# ts-50s-digi-interface.net
KiCad netlist of a schematic drawn in Altium Designer
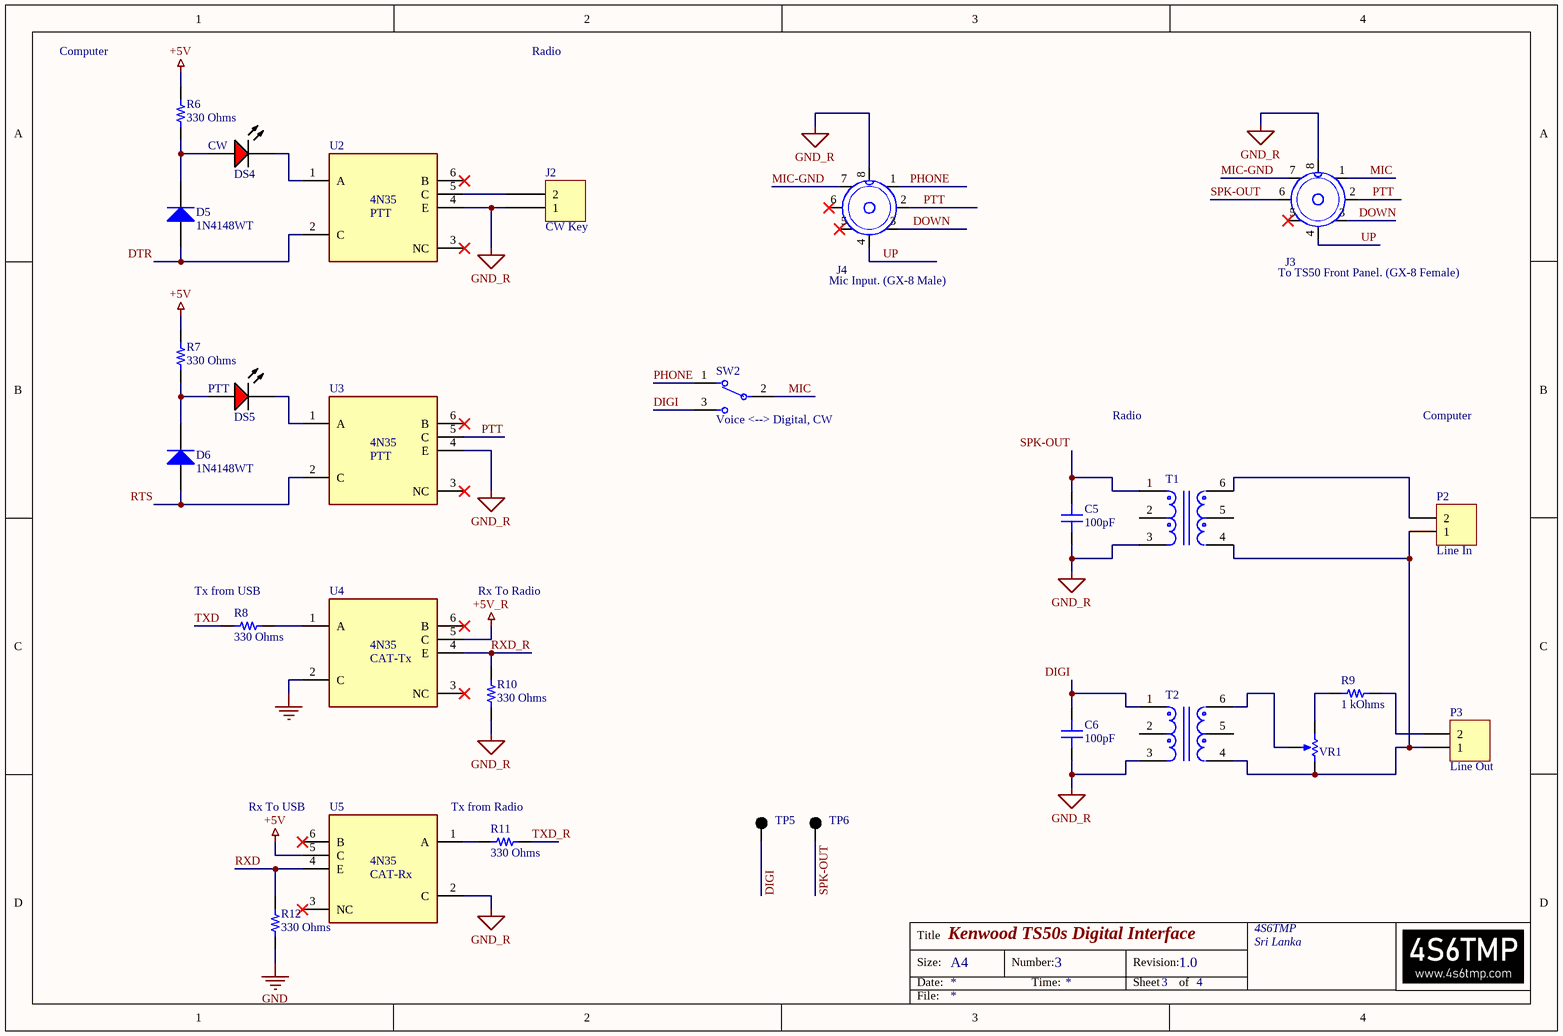
[diagram p0: ts-50s-digi-interface.SchDoc]

(export (version "E")
  (design (tool "Eeschema 10.0.6"))
  (components
    (comp (ref "C5")
      (value "100pF")
      (footprint "CAP 0603_1608")
      (description "CAP CER 100PF 50V C0G/NP0 0603")
      (fields
        (field (name "PART NUMBER") "500R14N101JV4T")
        (field (name "MANUFACTURER") "Johanson Dielectrics Inc.")
      )
      (libsource (lib "Celestial Altium Library - altium_library") (part "Capacitor"))
    )
    (comp (ref "C6")
      (value "100pF")
      (footprint "CAP 0603_1608")
      (description "CAP CER 100PF 50V C0G/NP0 0603")
      (fields
        (field (name "PART NUMBER") "500R14N101JV4T")
        (field (name "MANUFACTURER") "Johanson Dielectrics Inc.")
      )
      (libsource (lib "Celestial Altium Library - altium_library") (part "Capacitor"))
    )
    (comp (ref "D5")
      (value "1N4148WT")
      (footprint "FAIR-SOD-523F-2_V")
      (description "High Conductance Fast Switching Diode, 75 V, -55 to 150 degC, 2-Pin SOD523F, RoHS")
      (fields (field (name "MANUFACTURER") "Fairchild Semiconductor"))
      (libsource (lib "Altium Content Vault") (part "FAIR-D_K1A2-2"))
    )
    (comp (ref "D6")
      (value "1N4148WT")
      (footprint "FAIR-SOD-523F-2_V")
      (description "High Conductance Fast Switching Diode, 75 V, -55 to 150 degC, 2-Pin SOD523F, RoHS")
      (fields (field (name "MANUFACTURER") "Fairchild Semiconductor"))
      (libsource (lib "Altium Content Vault") (part "FAIR-D_K1A2-2"))
    )
    (comp (ref "DS4")
      (value "CW")
      (footprint "AVAG-HLMP-3301-2")
      (description "T-1 3/4 (5 mm) Diffused LED Lamp, 1.9 V, -40 to 100 degC, 2-Pin THD, RoHS, Bulk")
      (fields (field (name "MANUFACTURER") "Avago"))
      (libsource (lib "Altium Content Vault") (part "LED-RED-K1A2-2"))
    )
    (comp (ref "DS5")
      (value "PTT")
      (footprint "AVAG-HLMP-3301-2")
      (description "T-1 3/4 (5 mm) Diffused LED Lamp, 1.9 V, -40 to 100 degC, 2-Pin THD, RoHS, Bulk")
      (fields (field (name "MANUFACTURER") "Avago"))
      (libsource (lib "Altium Content Vault") (part "LED-RED-K1A2-2"))
    )
    (comp (ref "J2")
      (value "CW Key")
      (footprint "MOLEX KK 0022272021")
      (description "CONN HEADER VERT 2POS 2.54MM")
      (fields (field (name "PART NUMBER") "0022272021") (field (name "MANUFACTURER") "Molex"))
      (libsource (lib "Celestial Altium Library - altium_library") (part "2 Pin"))
    )
    (comp (ref "J3")
      (value "To TS50 Front Panel. (GX-8 Female)")
      (footprint "GX-8")
      (description "8 Position Circular Connector Receptacle, Male Pins Solder")
      (fields (field (name "MANUFACTURER") "Amphenol Tuchel Industrial"))
      (libsource (lib "GX-8") (part "GX-8"))
    )
    (comp (ref "J4")
      (value "Mic Input. (GX-8 Male)")
      (footprint "GX-8")
      (description "8 Position Circular Connector Receptacle, Male Pins Solder")
      (fields (field (name "MANUFACTURER") "Amphenol Tuchel Industrial"))
      (libsource (lib "GX-8") (part "GX-8"))
    )
    (comp (ref "P2")
      (value "Line In")
      (footprint "HDR1X2")
      (description "3.5mm Mono")
      (fields (field (name "PUBLISHER") "Altium Limited"))
      (libsource (lib "Miscellaneous Connectors") (part "Header 2"))
    )
    (comp (ref "P3")
      (value "Line Out")
      (footprint "HDR1X2")
      (description "3.5mm Mono")
      (fields (field (name "PUBLISHER") "Altium Limited"))
      (libsource (lib "Miscellaneous Connectors") (part "Header 2"))
    )
    (comp (ref "R6")
      (value "330 Ohms")
      (footprint "RES 0603_1608")
      (description "RES SMD 330 OHM 1% 1/10W 0603")
      (fields (field (name "PART NUMBER") "AC0603FR-07330RL") (field (name "MANUFACTURER") "Yageo"))
      (libsource (lib "Celestial Altium Library - altium_library") (part "Resistor"))
    )
    (comp (ref "R7")
      (value "330 Ohms")
      (footprint "RES 0603_1608")
      (description "RES SMD 330 OHM 1% 1/10W 0603")
      (fields (field (name "PART NUMBER") "AC0603FR-07330RL") (field (name "MANUFACTURER") "Yageo"))
      (libsource (lib "Celestial Altium Library - altium_library") (part "Resistor"))
    )
    (comp (ref "R8")
      (value "330 Ohms")
      (footprint "RES 0603_1608")
      (description "RES SMD 330 OHM 1% 1/10W 0603")
      (fields (field (name "PART NUMBER") "AC0603FR-07330RL") (field (name "MANUFACTURER") "Yageo"))
      (libsource (lib "Celestial Altium Library - altium_library") (part "Resistor"))
    )
    (comp (ref "R9")
      (value "1 kOhms")
      (footprint "RES 0603_1608")
      (description "RES SMD 1K OHM 1% 1/10W 0603")
      (fields (field (name "PART NUMBER") "AT0603FRE071KL") (field (name "MANUFACTURER") "Yageo"))
      (libsource (lib "Celestial Altium Library - altium_library") (part "Resistor"))
    )
    (comp (ref "R10")
      (value "330 Ohms")
      (footprint "RES 0603_1608")
      (description "RES SMD 330 OHM 1% 1/10W 0603")
      (fields (field (name "PART NUMBER") "AC0603FR-07330RL") (field (name "MANUFACTURER") "Yageo"))
      (libsource (lib "Celestial Altium Library - altium_library") (part "Resistor"))
    )
    (comp (ref "R11")
      (value "330 Ohms")
      (footprint "RES 0603_1608")
      (description "RES SMD 330 OHM 1% 1/10W 0603")
      (fields (field (name "PART NUMBER") "AC0603FR-07330RL") (field (name "MANUFACTURER") "Yageo"))
      (libsource (lib "Celestial Altium Library - altium_library") (part "Resistor"))
    )
    (comp (ref "R12")
      (value "330 Ohms")
      (footprint "RES 0603_1608")
      (description "RES SMD 330 OHM 1% 1/10W 0603")
      (fields (field (name "PART NUMBER") "AC0603FR-07330RL") (field (name "MANUFACTURER") "Yageo"))
      (libsource (lib "Celestial Altium Library - altium_library") (part "Resistor"))
    )
    (comp (ref "SW2")
      (value "Voice <--> Digital, CW")
      (footprint "FP-A101SDCQ04-MFG")
      (description "SWITCH TOGGLE SPDT 5A 120V")
      (libsource (lib "Altium Content Vault") (part "52c419afdc2a387c7d548259a9aeefb"))
    )
    (comp (ref "T1")
      (value "SM-LP-5001")
      (footprint "SM-LP-5001")
      (description "TRANSFORMER LINE MATCHING SMD")
      (libsource (lib "SM-LP-5001") (part "CMP-07264-000002-1"))
    )
    (comp (ref "T2")
      (value "SM-LP-5001")
      (footprint "SM-LP-5001")
      (description "TRANSFORMER LINE MATCHING SMD")
      (libsource (lib "SM-LP-5001") (part "CMP-07264-000002-1"))
    )
    (comp (ref "TP5")
      (value "DIGI")
      (footprint "KSTN-5001")
      (description "Test Point, Black, 1-Pin THD, RoHS, Bulk")
      (fields (field (name "MANUFACTURER") "Keystone"))
      (libsource (lib "Altium Content Vault") (part "KSTN-TP-5001"))
    )
    (comp (ref "TP6")
      (value "SPK OUT")
      (footprint "KSTN-5001")
      (description "Test Point, Black, 1-Pin THD, RoHS, Bulk")
      (fields (field (name "MANUFACTURER") "Keystone"))
      (libsource (lib "Altium Content Vault") (part "KSTN-TP-5001"))
    )
    (comp (ref "U2")
      (value "PTT")
      (footprint "Vishay_4N35_0")
      (description "IC OPTOISO 5KV TRANS W/BASE 6DIP")
      (fields
        (field (name "MANUFACTURER") "Vishay")
        (field (name "MOUSER PART NUMBER") "78-4N35")
        (field (name "PART NUMBER") "4N35")
      )
      (libsource (lib "") (part "IC_Vishay_4N35_eec_1"))
    )
    (comp (ref "U3")
      (value "PTT")
      (footprint "Vishay_4N35_0")
      (description "IC OPTOISO 5KV TRANS W/BASE 6DIP")
      (fields
        (field (name "MANUFACTURER") "Vishay")
        (field (name "MOUSER PART NUMBER") "78-4N35")
        (field (name "PART NUMBER") "4N35")
      )
      (libsource (lib "") (part "IC_Vishay_4N35_eec_1"))
    )
    (comp (ref "U4")
      (value "CAT-Tx")
      (footprint "Vishay_4N35_0")
      (description "IC OPTOISO 5KV TRANS W/BASE 6DIP")
      (fields
        (field (name "MANUFACTURER") "Vishay")
        (field (name "MOUSER PART NUMBER") "78-4N35")
        (field (name "PART NUMBER") "4N35")
      )
      (libsource (lib "") (part "IC_Vishay_4N35_eec_1"))
    )
    (comp (ref "U5")
      (value "CAT-Rx")
      (footprint "Vishay_4N35_0")
      (description "IC OPTOISO 5KV TRANS W/BASE 6DIP")
      (fields
        (field (name "MANUFACTURER") "Vishay")
        (field (name "MOUSER PART NUMBER") "78-4N35")
        (field (name "PART NUMBER") "4N35")
      )
      (libsource (lib "Optocouplers") (part "IC_Vishay_4N35_eec"))
    )
    (comp (ref "VR1")
      (value "3852A-282-103AL")
      (footprint "BOUR-3852A-282-103AL-3_V")
      (description "Diameter Panel Control, 100 KOhm, +/- 10%, 2 W, -1 to 125 degC, 3-Pin THD, RoHS, Bulk")
      (fields (field (name "TOLERANCE") "±10%") (field (name "MANUFACTURER") "Bourns"))
      (libsource (lib "Altium Content Vault") (part "RES-POT-3"))
    )
  )
  (nets
    (net (code "1") (name "+5V") (class "Default")
      (node (ref "R6") (pin "2") (pinfunction "2_2") (pintype "passive"))
      (node (ref "R7") (pin "2") (pinfunction "2_2") (pintype "passive"))
      (node (ref "U5") (pin "5") (pinfunction "C_5") (pintype "passive"))
    )
    (net (code "2") (name "+5V_R") (class "Default")
      (node (ref "U4") (pin "5") (pinfunction "C_5") (pintype "passive"))
    )
    (net (code "3") (name "/DIGI") (class "Default")
      (node (ref "C6") (pin "2") (pinfunction "2_2") (pintype "passive"))
      (node (ref "SW2") (pin "3") (pinfunction "3_3") (pintype "passive"))
      (node (ref "T2") (pin "1") (pinfunction "1_1") (pintype "passive"))
      (node (ref "TP5") (pin "1") (pintype "passive"))
    )
    (net (code "4") (name "/DOWN") (class "Default")
      (node (ref "J3") (pin "3") (pinfunction "3_3") (pintype "passive"))
      (node (ref "J4") (pin "3") (pinfunction "3_3") (pintype "passive"))
    )
    (net (code "5") (name "/DTR") (class "Default")
      (node (ref "D5") (pin "2") (pinfunction "A_2") (pintype "passive"))
      (node (ref "U2") (pin "2") (pinfunction "C_2") (pintype "passive"))
    )
    (net (code "6") (name "/MIC") (class "Default")
      (node (ref "J3") (pin "1") (pinfunction "1_1") (pintype "passive"))
      (node (ref "SW2") (pin "2") (pinfunction "2_2") (pintype "passive"))
    )
    (net (code "7") (name "/MIC-GND") (class "Default")
      (node (ref "J3") (pin "7") (pinfunction "7_7") (pintype "passive"))
      (node (ref "J4") (pin "7") (pinfunction "7_7") (pintype "passive"))
    )
    (net (code "8") (name "/PHONE") (class "Default")
      (node (ref "J4") (pin "1") (pinfunction "1_1") (pintype "passive"))
      (node (ref "SW2") (pin "1") (pinfunction "1_1") (pintype "passive"))
    )
    (net (code "9") (name "/PTT") (class "Default")
      (node (ref "J3") (pin "2") (pinfunction "2_2") (pintype "passive"))
      (node (ref "J4") (pin "2") (pinfunction "2_2") (pintype "passive"))
      (node (ref "U3") (pin "5") (pinfunction "C_5") (pintype "passive"))
    )
    (net (code "10") (name "/RTS") (class "Default")
      (node (ref "D6") (pin "2") (pinfunction "A_2") (pintype "passive"))
      (node (ref "U3") (pin "2") (pinfunction "C_2") (pintype "passive"))
    )
    (net (code "11") (name "/RXD") (class "Default")
      (node (ref "R12") (pin "1") (pinfunction "1_1") (pintype "passive"))
      (node (ref "U5") (pin "4") (pinfunction "E_4") (pintype "passive"))
    )
    (net (code "12") (name "/RXD_R") (class "Default")
      (node (ref "R10") (pin "1") (pinfunction "1_1") (pintype "passive"))
      (node (ref "U4") (pin "4") (pinfunction "E_4") (pintype "passive"))
    )
    (net (code "13") (name "/SPK-OUT") (class "Default")
      (node (ref "C5") (pin "2") (pinfunction "2_2") (pintype "passive"))
      (node (ref "J3") (pin "6") (pinfunction "6_6") (pintype "passive"))
      (node (ref "T1") (pin "1") (pinfunction "1_1") (pintype "passive"))
      (node (ref "TP6") (pin "1") (pintype "passive"))
    )
    (net (code "14") (name "/TXD") (class "Default")
      (node (ref "R8") (pin "2") (pinfunction "2_2") (pintype "passive"))
    )
    (net (code "15") (name "/TXD_R") (class "Default")
      (node (ref "R11") (pin "1") (pinfunction "1_1") (pintype "passive"))
    )
    (net (code "16") (name "/UP") (class "Default")
      (node (ref "J3") (pin "4") (pinfunction "4_4") (pintype "passive"))
      (node (ref "J4") (pin "4") (pinfunction "4_4") (pintype "passive"))
    )
    (net (code "17") (name "GND") (class "Default")
      (node (ref "R12") (pin "2") (pinfunction "2_2") (pintype "passive"))
      (node (ref "U4") (pin "2") (pinfunction "C_2") (pintype "passive"))
    )
    (net (code "18") (name "GND_R") (class "Default")
      (node (ref "C5") (pin "1") (pinfunction "1_1") (pintype "passive"))
      (node (ref "C6") (pin "1") (pinfunction "1_1") (pintype "passive"))
      (node (ref "J2") (pin "1") (pinfunction "1_1") (pintype "passive"))
      (node (ref "J3") (pin "8") (pinfunction "8_8") (pintype "passive"))
      (node (ref "J4") (pin "8") (pinfunction "8_8") (pintype "passive"))
      (node (ref "R10") (pin "2") (pinfunction "2_2") (pintype "passive"))
      (node (ref "T1") (pin "3") (pinfunction "3_3") (pintype "passive"))
      (node (ref "T2") (pin "3") (pinfunction "3_3") (pintype "passive"))
      (node (ref "U2") (pin "4") (pinfunction "E_4") (pintype "passive"))
      (node (ref "U3") (pin "4") (pinfunction "E_4") (pintype "passive"))
      (node (ref "U5") (pin "2") (pinfunction "C_2") (pintype "passive"))
    )
    (net (code "19") (name "Net-(D5-K)") (class "Default")
      (node (ref "D5") (pin "1") (pinfunction "K_1") (pintype "passive"))
      (node (ref "DS4") (pin "2") (pinfunction "A_2") (pintype "passive"))
      (node (ref "R6") (pin "1") (pinfunction "1_1") (pintype "passive"))
    )
    (net (code "20") (name "Net-(D6-K)") (class "Default")
      (node (ref "D6") (pin "1") (pinfunction "K_1") (pintype "passive"))
      (node (ref "DS5") (pin "2") (pinfunction "A_2") (pintype "passive"))
      (node (ref "R7") (pin "1") (pinfunction "1_1") (pintype "passive"))
    )
    (net (code "21") (name "Net-(DS4-K)") (class "Default")
      (node (ref "DS4") (pin "1") (pinfunction "K_1") (pintype "passive"))
      (node (ref "U2") (pin "1") (pinfunction "A_1") (pintype "passive"))
    )
    (net (code "22") (name "Net-(DS5-K)") (class "Default")
      (node (ref "DS5") (pin "1") (pinfunction "K_1") (pintype "passive"))
      (node (ref "U3") (pin "1") (pinfunction "A_1") (pintype "passive"))
    )
    (net (code "23") (name "Net-(J2-Pad2)") (class "Default")
      (node (ref "J2") (pin "2") (pinfunction "2_2") (pintype "passive"))
      (node (ref "U2") (pin "5") (pinfunction "C_5") (pintype "passive"))
    )
    (net (code "24") (name "Net-(P2-Pad2)") (class "Default")
      (node (ref "P2") (pin "2") (pinfunction "2_2") (pintype "passive"))
      (node (ref "T1") (pin "6") (pinfunction "6_6") (pintype "passive"))
    )
    (net (code "25") (name "Net-(P3-Pad2)") (class "Default")
      (node (ref "P3") (pin "2") (pinfunction "2_2") (pintype "passive"))
      (node (ref "R9") (pin "2") (pinfunction "2_2") (pintype "passive"))
    )
    (net (code "26") (name "Net-(U4-A)") (class "Default")
      (node (ref "R8") (pin "1") (pinfunction "1_1") (pintype "passive"))
      (node (ref "U4") (pin "1") (pinfunction "A_1") (pintype "passive"))
    )
    (net (code "27") (name "Net-(U5-A)") (class "Default")
      (node (ref "R11") (pin "2") (pinfunction "2_2") (pintype "passive"))
      (node (ref "U5") (pin "1") (pinfunction "A_1") (pintype "passive"))
    )
    (net (code "28") (name "Net-(VR1-CCW)") (class "Default")
      (node (ref "R9") (pin "1") (pinfunction "1_1") (pintype "passive"))
      (node (ref "VR1") (pin "1") (pinfunction "CCW_1") (pintype "passive"))
    )
    (net (code "29") (name "Net-(VR1-CW)") (class "Default")
      (node (ref "P2") (pin "1") (pinfunction "1_1") (pintype "passive"))
      (node (ref "P3") (pin "1") (pinfunction "1_1") (pintype "passive"))
      (node (ref "T1") (pin "4") (pinfunction "4_4") (pintype "passive"))
      (node (ref "T2") (pin "4") (pinfunction "4_4") (pintype "passive"))
      (node (ref "VR1") (pin "3") (pinfunction "CW_3") (pintype "passive"))
    )
    (net (code "30") (name "Net-(VR1-S)") (class "Default")
      (node (ref "T2") (pin "6") (pinfunction "6_6") (pintype "passive"))
      (node (ref "VR1") (pin "2") (pinfunction "S_2") (pintype "passive"))
    )
    (net (code "31") (name "unconnected-(J3-Pad5)") (class "Default")
      (node (ref "J3") (pin "5") (pinfunction "5_5") (pintype "passive+no_connect"))
    )
    (net (code "32") (name "unconnected-(J4-Pad5)") (class "Default")
      (node (ref "J4") (pin "5") (pinfunction "5_5") (pintype "passive+no_connect"))
    )
    (net (code "33") (name "unconnected-(J4-Pad6)") (class "Default")
      (node (ref "J4") (pin "6") (pinfunction "6_6") (pintype "passive+no_connect"))
    )
    (net (code "34") (name "unconnected-(T1-Pad2)") (class "Default")
      (node (ref "T1") (pin "2") (pinfunction "2_2") (pintype "passive"))
    )
    (net (code "35") (name "unconnected-(T1-Pad5)") (class "Default")
      (node (ref "T1") (pin "5") (pinfunction "5_5") (pintype "passive"))
    )
    (net (code "36") (name "unconnected-(T2-Pad2)") (class "Default")
      (node (ref "T2") (pin "2") (pinfunction "2_2") (pintype "passive"))
    )
    (net (code "37") (name "unconnected-(T2-Pad5)") (class "Default")
      (node (ref "T2") (pin "5") (pinfunction "5_5") (pintype "passive"))
    )
    (net (code "38") (name "unconnected-(U2-B-Pad6)") (class "Default")
      (node (ref "U2") (pin "6") (pinfunction "B_6") (pintype "passive+no_connect"))
    )
    (net (code "39") (name "unconnected-(U2-NC-Pad3)") (class "Default")
      (node (ref "U2") (pin "3") (pinfunction "NC_3") (pintype "passive+no_connect"))
    )
    (net (code "40") (name "unconnected-(U3-B-Pad6)") (class "Default")
      (node (ref "U3") (pin "6") (pinfunction "B_6") (pintype "passive+no_connect"))
    )
    (net (code "41") (name "unconnected-(U3-NC-Pad3)") (class "Default")
      (node (ref "U3") (pin "3") (pinfunction "NC_3") (pintype "passive+no_connect"))
    )
    (net (code "42") (name "unconnected-(U4-B-Pad6)") (class "Default")
      (node (ref "U4") (pin "6") (pinfunction "B_6") (pintype "passive+no_connect"))
    )
    (net (code "43") (name "unconnected-(U4-NC-Pad3)") (class "Default")
      (node (ref "U4") (pin "3") (pinfunction "NC_3") (pintype "passive+no_connect"))
    )
    (net (code "44") (name "unconnected-(U5-B-Pad6)") (class "Default")
      (node (ref "U5") (pin "6") (pinfunction "B_6") (pintype "passive+no_connect"))
    )
    (net (code "45") (name "unconnected-(U5-NC-Pad3)") (class "Default")
      (node (ref "U5") (pin "3") (pinfunction "NC_3") (pintype "passive+no_connect"))
    )
  )
)
